# platine.net
KiCad netlist of a schematic drawn in EAGLE
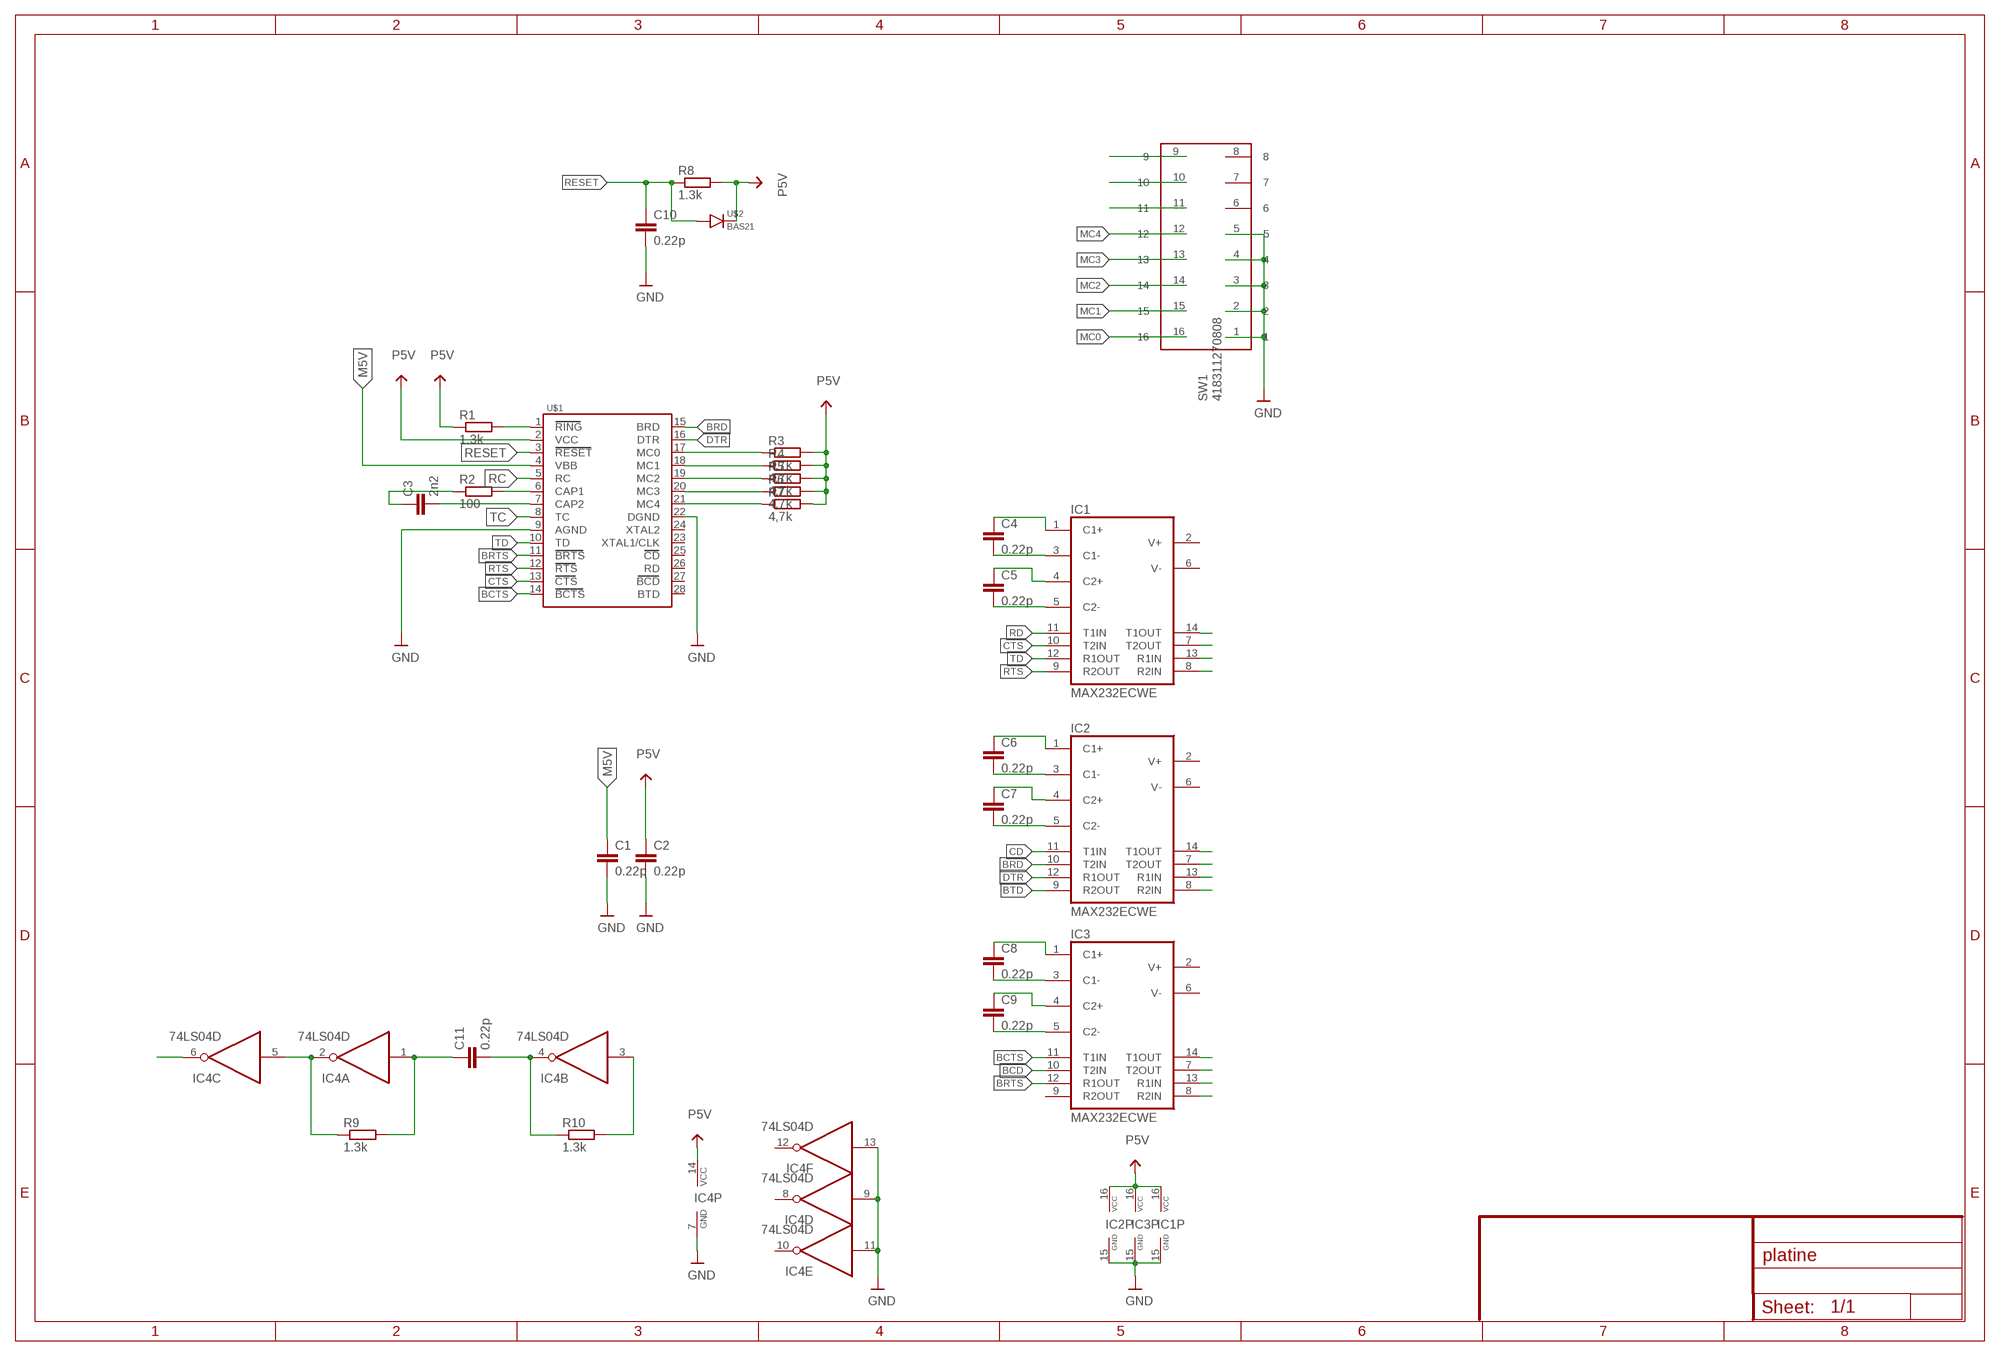
[diagram p0: schematic, sheet 1]

(export (version "E")
  (design (tool "Eeschema 10.0.6"))
  (components
    (comp (ref "C1")
      (value "0.22p")
      (footprint "eagle-import:C0805")
      (libsource (lib "eagle-import") (part "C-EUC0805"))
    )
    (comp (ref "C2")
      (value "0.22p")
      (footprint "eagle-import:C0805")
      (libsource (lib "eagle-import") (part "C-EUC0805"))
    )
    (comp (ref "C3")
      (value "2n2")
      (footprint "eagle-import:C0805")
      (libsource (lib "eagle-import") (part "C-EUC0805"))
    )
    (comp (ref "C4")
      (value "0.22p")
      (footprint "eagle-import:C0805")
      (libsource (lib "eagle-import") (part "C-EUC0805"))
    )
    (comp (ref "C5")
      (value "0.22p")
      (footprint "eagle-import:C0805")
      (libsource (lib "eagle-import") (part "C-EUC0805"))
    )
    (comp (ref "C6")
      (value "0.22p")
      (footprint "eagle-import:C0805")
      (libsource (lib "eagle-import") (part "C-EUC0805"))
    )
    (comp (ref "C7")
      (value "0.22p")
      (footprint "eagle-import:C0805")
      (libsource (lib "eagle-import") (part "C-EUC0805"))
    )
    (comp (ref "C8")
      (value "0.22p")
      (footprint "eagle-import:C0805")
      (libsource (lib "eagle-import") (part "C-EUC0805"))
    )
    (comp (ref "C9")
      (value "0.22p")
      (footprint "eagle-import:C0805")
      (libsource (lib "eagle-import") (part "C-EUC0805"))
    )
    (comp (ref "C10")
      (value "0.22p")
      (footprint "eagle-import:C0805")
      (libsource (lib "eagle-import") (part "C-EUC0805"))
    )
    (comp (ref "C11")
      (value "0.22p")
      (footprint "eagle-import:C0805")
      (libsource (lib "eagle-import") (part "C-EUC0805"))
    )
    (comp (ref "IC1")
      (value "MAX232ECWE")
      (footprint "eagle-import:SO16L")
      (fields (field (name "MF") "MAXIM") (field (name "MPN") "MAX232ECWE+"))
      (libsource (lib "eagle-import") (part "MAX232ECWE"))
    )
    (comp (ref "IC2")
      (value "MAX232ECWE")
      (footprint "eagle-import:SO16L")
      (fields (field (name "MF") "MAXIM") (field (name "MPN") "MAX232ECWE+"))
      (libsource (lib "eagle-import") (part "MAX232ECWE"))
    )
    (comp (ref "IC3")
      (value "MAX232ECWE")
      (footprint "eagle-import:SO16L")
      (fields (field (name "MF") "MAXIM") (field (name "MPN") "MAX232ECWE+"))
      (libsource (lib "eagle-import") (part "MAX232ECWE"))
    )
    (comp (ref "IC4")
      (value "74LS04D")
      (footprint "eagle-import:SO14")
      (libsource (lib "eagle-import") (part "7404DLS"))
    )
    (comp (ref "R1")
      (value "1.3k")
      (footprint "eagle-import:R0805")
      (libsource (lib "eagle-import") (part "R-EU_R0805"))
    )
    (comp (ref "R2")
      (value "100")
      (footprint "eagle-import:R0805")
      (libsource (lib "eagle-import") (part "R-EU_R0805"))
    )
    (comp (ref "R3")
      (value "4,7k")
      (footprint "eagle-import:R0805")
      (libsource (lib "eagle-import") (part "R-EU_R0805"))
    )
    (comp (ref "R4")
      (value "4,7k")
      (footprint "eagle-import:R0805")
      (libsource (lib "eagle-import") (part "R-EU_R0805"))
    )
    (comp (ref "R5")
      (value "4,7k")
      (footprint "eagle-import:R0805")
      (libsource (lib "eagle-import") (part "R-EU_R0805"))
    )
    (comp (ref "R6")
      (value "4,7k")
      (footprint "eagle-import:R0805")
      (libsource (lib "eagle-import") (part "R-EU_R0805"))
    )
    (comp (ref "R7")
      (value "4,7k")
      (footprint "eagle-import:R0805")
      (libsource (lib "eagle-import") (part "R-EU_R0805"))
    )
    (comp (ref "R8")
      (value "1.3k")
      (footprint "eagle-import:R0805")
      (libsource (lib "eagle-import") (part "R-EU_R0805"))
    )
    (comp (ref "R9")
      (value "1.3k")
      (footprint "eagle-import:R0805")
      (libsource (lib "eagle-import") (part "R-EU_R0805"))
    )
    (comp (ref "R10")
      (value "1.3k")
      (footprint "eagle-import:R0805")
      (libsource (lib "eagle-import") (part "R-EU_R0805"))
    )
    (comp (ref "SW1")
      (value "418311270808")
      (footprint "eagle-import:418311270808")
      (libsource (lib "eagle-import") (part "418311270808"))
    )
    (comp (ref "U$1")
      (value "AM7910")
      (footprint "eagle-import:DIL28-6")
      (libsource (lib "eagle-import") (part "AM7910"))
    )
    (comp (ref "U$2")
      (value "BAS21")
      (footprint "eagle-import:SOT23")
      (libsource (lib "eagle-import") (part "BAS21"))
    )
  )
  (nets
    (net (code "1") (name "BCD") (class "Default")
      (node (ref "IC3") (pin "10") (pinfunction "T2IN_10") (pintype "input"))
    )
    (net (code "2") (name "BCTS") (class "Default")
      (node (ref "IC3") (pin "11") (pinfunction "T1IN_11") (pintype "input"))
      (node (ref "U$1") (pin "14") (pinfunction "BCTS_14") (pintype "bidirectional"))
    )
    (net (code "3") (name "BRD") (class "Default")
      (node (ref "IC2") (pin "10") (pinfunction "T2IN_10") (pintype "input"))
      (node (ref "U$1") (pin "15") (pinfunction "BRD_15") (pintype "bidirectional"))
    )
    (net (code "4") (name "BRTS") (class "Default")
      (node (ref "IC3") (pin "12") (pinfunction "R1OUT_12") (pintype "output"))
      (node (ref "U$1") (pin "11") (pinfunction "BRTS_11") (pintype "bidirectional"))
    )
    (net (code "5") (name "BTD") (class "Default")
      (node (ref "IC2") (pin "9") (pinfunction "R2OUT_9") (pintype "output"))
    )
    (net (code "6") (name "CD") (class "Default")
      (node (ref "IC2") (pin "11") (pinfunction "T1IN_11") (pintype "input"))
    )
    (net (code "7") (name "CTS") (class "Default")
      (node (ref "IC1") (pin "10") (pinfunction "T2IN_10") (pintype "input"))
      (node (ref "U$1") (pin "13") (pinfunction "CTS_13") (pintype "bidirectional"))
    )
    (net (code "8") (name "DTR") (class "Default")
      (node (ref "IC2") (pin "12") (pinfunction "R1OUT_12") (pintype "output"))
      (node (ref "U$1") (pin "16") (pinfunction "DTR_16") (pintype "bidirectional"))
    )
    (net (code "9") (name "GND") (class "Default")
      (node (ref "C1") (pin "2") (pinfunction "2_2") (pintype "passive"))
      (node (ref "C10") (pin "2") (pinfunction "2_2") (pintype "passive"))
      (node (ref "C2") (pin "2") (pinfunction "2_2") (pintype "passive"))
      (node (ref "IC1") (pin "15") (pinfunction "GND_15") (pintype "power_in"))
      (node (ref "IC2") (pin "15") (pinfunction "GND_15") (pintype "power_in"))
      (node (ref "IC3") (pin "15") (pinfunction "GND_15") (pintype "power_in"))
      (node (ref "IC4") (pin "11") (pinfunction "I_11") (pintype "input"))
      (node (ref "IC4") (pin "13") (pinfunction "I_13") (pintype "input"))
      (node (ref "IC4") (pin "7") (pinfunction "GND_7") (pintype "power_in"))
      (node (ref "IC4") (pin "9") (pinfunction "I_9") (pintype "input"))
      (node (ref "SW1") (pin "1") (pinfunction "1_1") (pintype "bidirectional"))
      (node (ref "SW1") (pin "2") (pinfunction "2_2") (pintype "bidirectional"))
      (node (ref "SW1") (pin "3") (pinfunction "3_3") (pintype "bidirectional"))
      (node (ref "SW1") (pin "4") (pinfunction "4_4") (pintype "bidirectional"))
      (node (ref "SW1") (pin "5") (pinfunction "5_5") (pintype "bidirectional"))
      (node (ref "U$1") (pin "22") (pinfunction "DGND_22") (pintype "bidirectional"))
      (node (ref "U$1") (pin "9") (pinfunction "AGND_9") (pintype "bidirectional"))
    )
    (net (code "10") (name "M5V") (class "Default")
      (node (ref "C1") (pin "1") (pinfunction "1_1") (pintype "passive"))
      (node (ref "U$1") (pin "4") (pinfunction "VBB_4") (pintype "bidirectional"))
    )
    (net (code "11") (name "MC0") (class "Default")
      (node (ref "R3") (pin "1") (pinfunction "1_1") (pintype "passive"))
      (node (ref "SW1") (pin "16") (pinfunction "16_16") (pintype "bidirectional"))
      (node (ref "U$1") (pin "17") (pinfunction "MC0_17") (pintype "bidirectional"))
    )
    (net (code "12") (name "MC1") (class "Default")
      (node (ref "R4") (pin "1") (pinfunction "1_1") (pintype "passive"))
      (node (ref "SW1") (pin "15") (pinfunction "15_15") (pintype "bidirectional"))
      (node (ref "U$1") (pin "18") (pinfunction "MC1_18") (pintype "bidirectional"))
    )
    (net (code "13") (name "MC2") (class "Default")
      (node (ref "R5") (pin "1") (pinfunction "1_1") (pintype "passive"))
      (node (ref "SW1") (pin "14") (pinfunction "14_14") (pintype "bidirectional"))
      (node (ref "U$1") (pin "19") (pinfunction "MC2_19") (pintype "bidirectional"))
    )
    (net (code "14") (name "MC3") (class "Default")
      (node (ref "R6") (pin "1") (pinfunction "1_1") (pintype "passive"))
      (node (ref "SW1") (pin "13") (pinfunction "13_13") (pintype "bidirectional"))
      (node (ref "U$1") (pin "20") (pinfunction "MC3_20") (pintype "bidirectional"))
    )
    (net (code "15") (name "MC4") (class "Default")
      (node (ref "R7") (pin "1") (pinfunction "1_1") (pintype "passive"))
      (node (ref "SW1") (pin "11") (pinfunction "11_11") (pintype "bidirectional"))
      (node (ref "SW1") (pin "12") (pinfunction "12_12") (pintype "bidirectional"))
      (node (ref "U$1") (pin "21") (pinfunction "MC4_21") (pintype "bidirectional"))
    )
    (net (code "16") (name "Net-(C3-Pad1)") (class "Default")
      (node (ref "C3") (pin "1") (pinfunction "1_1") (pintype "passive"))
      (node (ref "R2") (pin "1") (pinfunction "1_1") (pintype "passive"))
    )
    (net (code "17") (name "Net-(IC1A-C1+)") (class "Default")
      (node (ref "C4") (pin "1") (pinfunction "1_1") (pintype "passive"))
      (node (ref "IC1") (pin "1") (pinfunction "C1+_1") (pintype "bidirectional"))
    )
    (net (code "18") (name "Net-(IC1A-C1-)") (class "Default")
      (node (ref "C4") (pin "2") (pinfunction "2_2") (pintype "passive"))
      (node (ref "IC1") (pin "3") (pinfunction "C1-_3") (pintype "bidirectional"))
    )
    (net (code "19") (name "Net-(IC1A-C2+)") (class "Default")
      (node (ref "C5") (pin "1") (pinfunction "1_1") (pintype "passive"))
      (node (ref "IC1") (pin "4") (pinfunction "C2+_4") (pintype "bidirectional"))
    )
    (net (code "20") (name "Net-(IC1A-C2-)") (class "Default")
      (node (ref "C5") (pin "2") (pinfunction "2_2") (pintype "passive"))
      (node (ref "IC1") (pin "5") (pinfunction "C2-_5") (pintype "bidirectional"))
    )
    (net (code "21") (name "Net-(IC2A-C1+)") (class "Default")
      (node (ref "C6") (pin "1") (pinfunction "1_1") (pintype "passive"))
      (node (ref "IC2") (pin "1") (pinfunction "C1+_1") (pintype "bidirectional"))
    )
    (net (code "22") (name "Net-(IC2A-C1-)") (class "Default")
      (node (ref "C6") (pin "2") (pinfunction "2_2") (pintype "passive"))
      (node (ref "IC2") (pin "3") (pinfunction "C1-_3") (pintype "bidirectional"))
    )
    (net (code "23") (name "Net-(IC2A-C2+)") (class "Default")
      (node (ref "C7") (pin "1") (pinfunction "1_1") (pintype "passive"))
      (node (ref "IC2") (pin "4") (pinfunction "C2+_4") (pintype "bidirectional"))
    )
    (net (code "24") (name "Net-(IC2A-C2-)") (class "Default")
      (node (ref "C7") (pin "2") (pinfunction "2_2") (pintype "passive"))
      (node (ref "IC2") (pin "5") (pinfunction "C2-_5") (pintype "bidirectional"))
    )
    (net (code "25") (name "Net-(IC3A-C1+)") (class "Default")
      (node (ref "C8") (pin "1") (pinfunction "1_1") (pintype "passive"))
      (node (ref "IC3") (pin "1") (pinfunction "C1+_1") (pintype "bidirectional"))
    )
    (net (code "26") (name "Net-(IC3A-C1-)") (class "Default")
      (node (ref "C8") (pin "2") (pinfunction "2_2") (pintype "passive"))
      (node (ref "IC3") (pin "3") (pinfunction "C1-_3") (pintype "bidirectional"))
    )
    (net (code "27") (name "Net-(IC3A-C2+)") (class "Default")
      (node (ref "C9") (pin "1") (pinfunction "1_1") (pintype "passive"))
      (node (ref "IC3") (pin "4") (pinfunction "C2+_4") (pintype "bidirectional"))
    )
    (net (code "28") (name "Net-(IC3A-C2-)") (class "Default")
      (node (ref "C9") (pin "2") (pinfunction "2_2") (pintype "passive"))
      (node (ref "IC3") (pin "5") (pinfunction "C2-_5") (pintype "bidirectional"))
    )
    (net (code "29") (name "Net-(IC4A-I)") (class "Default")
      (node (ref "C11") (pin "1") (pinfunction "1_1") (pintype "passive"))
      (node (ref "IC4") (pin "1") (pinfunction "I_1") (pintype "input"))
      (node (ref "R9") (pin "2") (pinfunction "2_2") (pintype "passive"))
    )
    (net (code "30") (name "Net-(IC4A-O)") (class "Default")
      (node (ref "IC4") (pin "2") (pinfunction "O_2") (pintype "output"))
      (node (ref "IC4") (pin "5") (pinfunction "I_5") (pintype "input"))
      (node (ref "R9") (pin "1") (pinfunction "1_1") (pintype "passive"))
    )
    (net (code "31") (name "Net-(IC4B-I)") (class "Default")
      (node (ref "IC4") (pin "3") (pinfunction "I_3") (pintype "input"))
      (node (ref "R10") (pin "2") (pinfunction "2_2") (pintype "passive"))
    )
    (net (code "32") (name "Net-(IC4B-O)") (class "Default")
      (node (ref "C11") (pin "2") (pinfunction "2_2") (pintype "passive"))
      (node (ref "IC4") (pin "4") (pinfunction "O_4") (pintype "output"))
      (node (ref "R10") (pin "1") (pinfunction "1_1") (pintype "passive"))
    )
    (net (code "33") (name "Net-(U$1-CAP1)") (class "Default")
      (node (ref "R2") (pin "2") (pinfunction "2_2") (pintype "passive"))
      (node (ref "U$1") (pin "6") (pinfunction "CAP1_6") (pintype "bidirectional"))
    )
    (net (code "34") (name "Net-(U$1-CAP2)") (class "Default")
      (node (ref "C3") (pin "2") (pinfunction "2_2") (pintype "passive"))
      (node (ref "U$1") (pin "7") (pinfunction "CAP2_7") (pintype "bidirectional"))
    )
    (net (code "35") (name "Net-(U$1-RING)") (class "Default")
      (node (ref "R1") (pin "2") (pinfunction "2_2") (pintype "passive"))
      (node (ref "U$1") (pin "1") (pinfunction "RING_1") (pintype "bidirectional"))
    )
    (net (code "36") (name "P5V") (class "Default")
      (node (ref "C2") (pin "1") (pinfunction "1_1") (pintype "passive"))
      (node (ref "IC1") (pin "16") (pinfunction "VCC_16") (pintype "power_in"))
      (node (ref "IC2") (pin "16") (pinfunction "VCC_16") (pintype "power_in"))
      (node (ref "IC3") (pin "16") (pinfunction "VCC_16") (pintype "power_in"))
      (node (ref "IC4") (pin "14") (pinfunction "VCC_14") (pintype "power_in"))
      (node (ref "R1") (pin "1") (pinfunction "1_1") (pintype "passive"))
      (node (ref "R3") (pin "2") (pinfunction "2_2") (pintype "passive"))
      (node (ref "R4") (pin "2") (pinfunction "2_2") (pintype "passive"))
      (node (ref "R5") (pin "2") (pinfunction "2_2") (pintype "passive"))
      (node (ref "R6") (pin "2") (pinfunction "2_2") (pintype "passive"))
      (node (ref "R7") (pin "2") (pinfunction "2_2") (pintype "passive"))
      (node (ref "R8") (pin "2") (pinfunction "2_2") (pintype "passive"))
      (node (ref "U$1") (pin "2") (pinfunction "VCC_2") (pintype "bidirectional"))
      (node (ref "U$2") (pin "3") (pinfunction "C_3") (pintype "bidirectional"))
    )
    (net (code "37") (name "RC") (class "Default")
      (node (ref "U$1") (pin "5") (pinfunction "RC_5") (pintype "bidirectional"))
    )
    (net (code "38") (name "RD") (class "Default")
      (node (ref "IC1") (pin "11") (pinfunction "T1IN_11") (pintype "input"))
    )
    (net (code "39") (name "RESET") (class "Default")
      (node (ref "C10") (pin "1") (pinfunction "1_1") (pintype "passive"))
      (node (ref "R8") (pin "1") (pinfunction "1_1") (pintype "passive"))
      (node (ref "U$1") (pin "3") (pinfunction "RESET_3") (pintype "bidirectional"))
      (node (ref "U$2") (pin "1") (pinfunction "A_1") (pintype "bidirectional"))
    )
    (net (code "40") (name "RTS") (class "Default")
      (node (ref "IC1") (pin "9") (pinfunction "R2OUT_9") (pintype "output"))
      (node (ref "U$1") (pin "12") (pinfunction "RTS_12") (pintype "bidirectional"))
    )
    (net (code "41") (name "TC") (class "Default")
      (node (ref "U$1") (pin "8") (pinfunction "TC_8") (pintype "bidirectional"))
    )
    (net (code "42") (name "TD") (class "Default")
      (node (ref "IC1") (pin "12") (pinfunction "R1OUT_12") (pintype "output"))
      (node (ref "U$1") (pin "10") (pinfunction "TD_10") (pintype "bidirectional"))
    )
    (net (code "43") (name "unconnected-(IC1A-R1IN-Pad13)") (class "Default")
      (node (ref "IC1") (pin "13") (pinfunction "R1IN_13") (pintype "input"))
    )
    (net (code "44") (name "unconnected-(IC1A-R2IN-Pad8)") (class "Default")
      (node (ref "IC1") (pin "8") (pinfunction "R2IN_8") (pintype "input"))
    )
    (net (code "45") (name "unconnected-(IC1A-T1OUT-Pad14)") (class "Default")
      (node (ref "IC1") (pin "14") (pinfunction "T1OUT_14") (pintype "output"))
    )
    (net (code "46") (name "unconnected-(IC1A-T2OUT-Pad7)") (class "Default")
      (node (ref "IC1") (pin "7") (pinfunction "T2OUT_7") (pintype "output"))
    )
    (net (code "47") (name "unconnected-(IC1A-V+-Pad2)") (class "Default")
      (node (ref "IC1") (pin "2") (pinfunction "V+_2") (pintype "bidirectional"))
    )
    (net (code "48") (name "unconnected-(IC1A-V--Pad6)") (class "Default")
      (node (ref "IC1") (pin "6") (pinfunction "V-_6") (pintype "bidirectional"))
    )
    (net (code "49") (name "unconnected-(IC2A-R1IN-Pad13)") (class "Default")
      (node (ref "IC2") (pin "13") (pinfunction "R1IN_13") (pintype "input"))
    )
    (net (code "50") (name "unconnected-(IC2A-R2IN-Pad8)") (class "Default")
      (node (ref "IC2") (pin "8") (pinfunction "R2IN_8") (pintype "input"))
    )
    (net (code "51") (name "unconnected-(IC2A-T1OUT-Pad14)") (class "Default")
      (node (ref "IC2") (pin "14") (pinfunction "T1OUT_14") (pintype "output"))
    )
    (net (code "52") (name "unconnected-(IC2A-T2OUT-Pad7)") (class "Default")
      (node (ref "IC2") (pin "7") (pinfunction "T2OUT_7") (pintype "output"))
    )
    (net (code "53") (name "unconnected-(IC2A-V+-Pad2)") (class "Default")
      (node (ref "IC2") (pin "2") (pinfunction "V+_2") (pintype "bidirectional"))
    )
    (net (code "54") (name "unconnected-(IC2A-V--Pad6)") (class "Default")
      (node (ref "IC2") (pin "6") (pinfunction "V-_6") (pintype "bidirectional"))
    )
    (net (code "55") (name "unconnected-(IC3A-R1IN-Pad13)") (class "Default")
      (node (ref "IC3") (pin "13") (pinfunction "R1IN_13") (pintype "input"))
    )
    (net (code "56") (name "unconnected-(IC3A-R2IN-Pad8)") (class "Default")
      (node (ref "IC3") (pin "8") (pinfunction "R2IN_8") (pintype "input"))
    )
    (net (code "57") (name "unconnected-(IC3A-R2OUT-Pad9)") (class "Default")
      (node (ref "IC3") (pin "9") (pinfunction "R2OUT_9") (pintype "output"))
    )
    (net (code "58") (name "unconnected-(IC3A-T1OUT-Pad14)") (class "Default")
      (node (ref "IC3") (pin "14") (pinfunction "T1OUT_14") (pintype "output"))
    )
    (net (code "59") (name "unconnected-(IC3A-T2OUT-Pad7)") (class "Default")
      (node (ref "IC3") (pin "7") (pinfunction "T2OUT_7") (pintype "output"))
    )
    (net (code "60") (name "unconnected-(IC3A-V+-Pad2)") (class "Default")
      (node (ref "IC3") (pin "2") (pinfunction "V+_2") (pintype "bidirectional"))
    )
    (net (code "61") (name "unconnected-(IC3A-V--Pad6)") (class "Default")
      (node (ref "IC3") (pin "6") (pinfunction "V-_6") (pintype "bidirectional"))
    )
    (net (code "62") (name "unconnected-(IC4C-O-Pad6)") (class "Default")
      (node (ref "IC4") (pin "6") (pinfunction "O_6") (pintype "output"))
    )
    (net (code "63") (name "unconnected-(IC4D-O-Pad8)") (class "Default")
      (node (ref "IC4") (pin "8") (pinfunction "O_8") (pintype "output"))
    )
    (net (code "64") (name "unconnected-(IC4E-O-Pad10)") (class "Default")
      (node (ref "IC4") (pin "10") (pinfunction "O_10") (pintype "output"))
    )
    (net (code "65") (name "unconnected-(IC4F-O-Pad12)") (class "Default")
      (node (ref "IC4") (pin "12") (pinfunction "O_12") (pintype "output"))
    )
    (net (code "66") (name "unconnected-(SW1-Pad6)") (class "Default")
      (node (ref "SW1") (pin "6") (pinfunction "6_6") (pintype "bidirectional"))
    )
    (net (code "67") (name "unconnected-(SW1-Pad7)") (class "Default")
      (node (ref "SW1") (pin "7") (pinfunction "7_7") (pintype "bidirectional"))
    )
    (net (code "68") (name "unconnected-(SW1-Pad8)") (class "Default")
      (node (ref "SW1") (pin "8") (pinfunction "8_8") (pintype "bidirectional"))
    )
    (net (code "69") (name "unconnected-(SW1-Pad9)") (class "Default")
      (node (ref "SW1") (pin "9") (pinfunction "9_9") (pintype "bidirectional"))
    )
    (net (code "70") (name "unconnected-(SW1-Pad10)") (class "Default")
      (node (ref "SW1") (pin "10") (pinfunction "10_10") (pintype "bidirectional"))
    )
    (net (code "71") (name "unconnected-(U$1-BCD-Pad27)") (class "Default")
      (node (ref "U$1") (pin "27") (pinfunction "BCD_27") (pintype "bidirectional"))
    )
    (net (code "72") (name "unconnected-(U$1-BTD-Pad28)") (class "Default")
      (node (ref "U$1") (pin "28") (pinfunction "BTD_28") (pintype "bidirectional"))
    )
    (net (code "73") (name "unconnected-(U$1-CD-Pad25)") (class "Default")
      (node (ref "U$1") (pin "25") (pinfunction "CD_25") (pintype "bidirectional"))
    )
    (net (code "74") (name "unconnected-(U$1-RD-Pad26)") (class "Default")
      (node (ref "U$1") (pin "26") (pinfunction "RD_26") (pintype "bidirectional"))
    )
    (net (code "75") (name "unconnected-(U$1-XTAL1{slash}CLK-Pad23)") (class "Default")
      (node (ref "U$1") (pin "23") (pinfunction "XTAL1/CLK_23") (pintype "bidirectional"))
    )
    (net (code "76") (name "unconnected-(U$1-XTAL2-Pad24)") (class "Default")
      (node (ref "U$1") (pin "24") (pinfunction "XTAL2_24") (pintype "bidirectional"))
    )
  )
)
